# p7_1_3v3.net
KiCad netlist of a schematic drawn in EAGLE
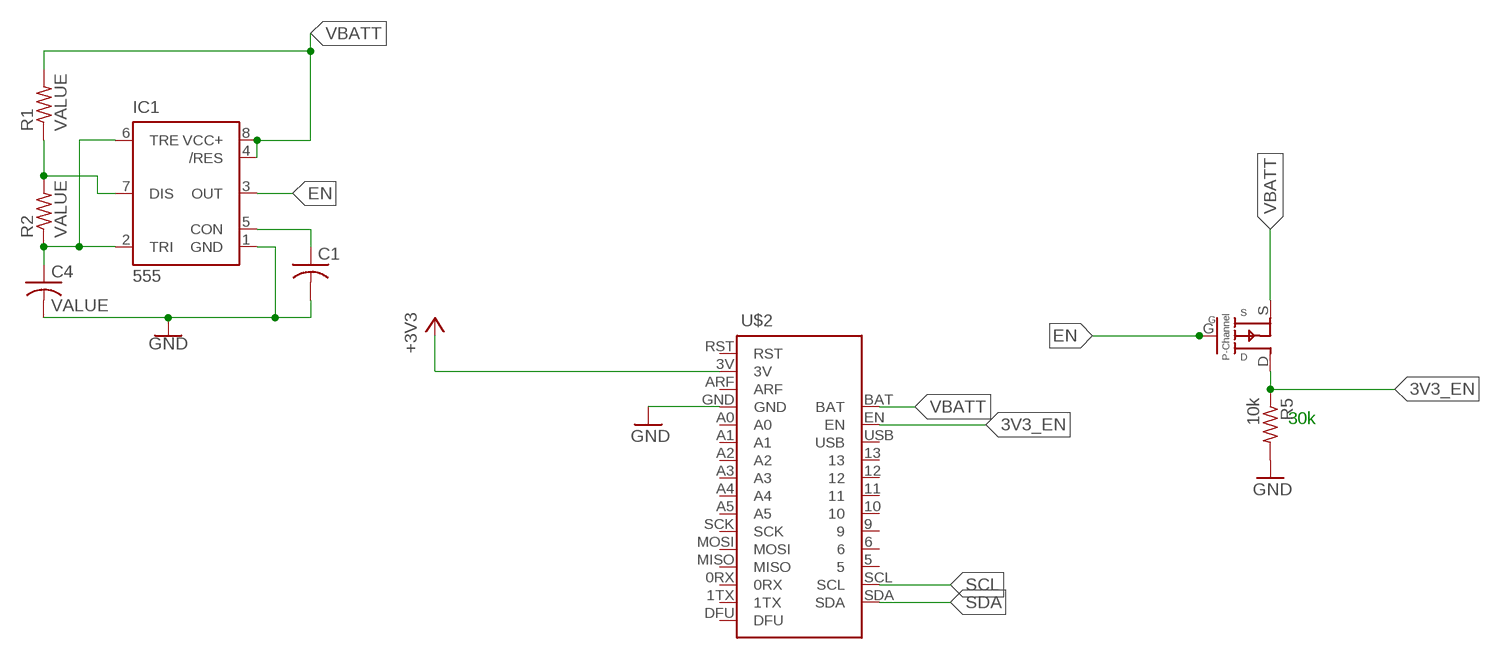
[diagram p0: schematic, sheet 1]

(export (version "E")
  (design (tool "Eeschema 10.0.6"))
  (components
    (comp (ref "C1")
      (value "C-USC1206")
      (footprint "eagle-import:C1206")
      (libsource (lib "eagle-import") (part "C-USC1206"))
    )
    (comp (ref "C4")
      (value "VALUE")
      (footprint "eagle-import:C1206")
      (libsource (lib "eagle-import") (part "C-USC1206"))
    )
    (comp (ref "IC1")
      (value "555")
      (footprint "eagle-import:DIP08")
      (libsource (lib "eagle-import") (part "555P"))
    )
    (comp (ref "Q2")
      (value "SSM3J3228R")
      (footprint "eagle-import:SOT-23-3")
      (libsource (lib "eagle-import") (part "SSM3J3228R"))
    )
    (comp (ref "R1")
      (value "VALUE")
      (footprint "eagle-import:R1206")
      (libsource (lib "eagle-import") (part "R-US_R1206"))
    )
    (comp (ref "R2")
      (value "VALUE")
      (footprint "eagle-import:R1206")
      (libsource (lib "eagle-import") (part "R-US_R1206"))
    )
    (comp (ref "R5")
      (value "10k")
      (footprint "eagle-import:R1206")
      (libsource (lib "eagle-import") (part "R-US_R1206"))
    )
    (comp (ref "U$2")
      (value "BLUEFRUIT_M0")
      (footprint "eagle-import:BLUEFRUIT_MO")
      (libsource (lib "eagle-import") (part "BLUEFRUIT_M0"))
    )
  )
  (nets
    (net (code "1") (name "+3V3") (class "Default")
      (node (ref "U$2") (pin "3V") (pinfunction "3V_3V") (pintype "bidirectional"))
    )
    (net (code "2") (name "3V3_EN") (class "Default")
      (node (ref "Q2") (pin "D") (pinfunction "D_D") (pintype "bidirectional"))
      (node (ref "R5") (pin "1") (pinfunction "1_1") (pintype "passive"))
      (node (ref "U$2") (pin "EN") (pinfunction "EN_EN") (pintype "bidirectional"))
    )
    (net (code "3") (name "EN") (class "Default")
      (node (ref "IC1") (pin "3") (pinfunction "OUT_3") (pintype "output"))
      (node (ref "Q2") (pin "G") (pinfunction "G_G") (pintype "bidirectional"))
    )
    (net (code "4") (name "GND") (class "Default")
      (node (ref "C1") (pin "2") (pinfunction "2_2") (pintype "passive"))
      (node (ref "C4") (pin "2") (pinfunction "2_2") (pintype "passive"))
      (node (ref "IC1") (pin "1") (pinfunction "GND_1") (pintype "power_in"))
      (node (ref "R5") (pin "2") (pinfunction "2_2") (pintype "passive"))
      (node (ref "U$2") (pin "GND") (pinfunction "GND_GND") (pintype "bidirectional"))
    )
    (net (code "5") (name "Net-(IC1-CON)") (class "Default")
      (node (ref "C1") (pin "1") (pinfunction "1_1") (pintype "passive"))
      (node (ref "IC1") (pin "5") (pinfunction "CON_5") (pintype "input"))
    )
    (net (code "6") (name "Net-(IC1-DIS)") (class "Default")
      (node (ref "IC1") (pin "7") (pinfunction "DIS_7") (pintype "input"))
      (node (ref "R1") (pin "1") (pinfunction "1_1") (pintype "passive"))
      (node (ref "R2") (pin "2") (pinfunction "2_2") (pintype "passive"))
    )
    (net (code "7") (name "Net-(IC1-TRE)") (class "Default")
      (node (ref "C4") (pin "1") (pinfunction "1_1") (pintype "passive"))
      (node (ref "IC1") (pin "2") (pinfunction "TRI_2") (pintype "input"))
      (node (ref "IC1") (pin "6") (pinfunction "TRE_6") (pintype "input"))
      (node (ref "R2") (pin "1") (pinfunction "1_1") (pintype "passive"))
    )
    (net (code "8") (name "SCL") (class "Default")
      (node (ref "U$2") (pin "SCL") (pinfunction "SCL_SCL") (pintype "bidirectional"))
    )
    (net (code "9") (name "SDA") (class "Default")
      (node (ref "U$2") (pin "SDA") (pinfunction "SDA_SDA") (pintype "bidirectional"))
    )
    (net (code "10") (name "VBATT") (class "Default")
      (node (ref "IC1") (pin "4") (pinfunction "/RES_4") (pintype "input"))
      (node (ref "IC1") (pin "8") (pinfunction "VCC+_8") (pintype "power_in"))
      (node (ref "Q2") (pin "S") (pinfunction "S_S") (pintype "bidirectional"))
      (node (ref "R1") (pin "2") (pinfunction "2_2") (pintype "passive"))
      (node (ref "U$2") (pin "BAT") (pinfunction "BAT_BAT") (pintype "bidirectional"))
    )
    (net (code "11") (name "unconnected-(U$2-Pad0RX)") (class "Default")
      (node (ref "U$2") (pin "0RX") (pinfunction "0RX_0RX") (pintype "bidirectional"))
    )
    (net (code "12") (name "unconnected-(U$2-Pad1TX)") (class "Default")
      (node (ref "U$2") (pin "1TX") (pinfunction "1TX_1TX") (pintype "bidirectional"))
    )
    (net (code "13") (name "unconnected-(U$2-Pad5)") (class "Default")
      (node (ref "U$2") (pin "5") (pinfunction "5_5") (pintype "bidirectional"))
    )
    (net (code "14") (name "unconnected-(U$2-Pad6)") (class "Default")
      (node (ref "U$2") (pin "6") (pinfunction "6_6") (pintype "bidirectional"))
    )
    (net (code "15") (name "unconnected-(U$2-Pad9)") (class "Default")
      (node (ref "U$2") (pin "9") (pinfunction "9_9") (pintype "bidirectional"))
    )
    (net (code "16") (name "unconnected-(U$2-Pad10)") (class "Default")
      (node (ref "U$2") (pin "10") (pinfunction "10_10") (pintype "bidirectional"))
    )
    (net (code "17") (name "unconnected-(U$2-Pad11)") (class "Default")
      (node (ref "U$2") (pin "11") (pinfunction "11_11") (pintype "bidirectional"))
    )
    (net (code "18") (name "unconnected-(U$2-Pad12)") (class "Default")
      (node (ref "U$2") (pin "12") (pinfunction "12_12") (pintype "bidirectional"))
    )
    (net (code "19") (name "unconnected-(U$2-Pad13)") (class "Default")
      (node (ref "U$2") (pin "13") (pinfunction "13_13") (pintype "bidirectional"))
    )
    (net (code "20") (name "unconnected-(U$2-PadA0)") (class "Default")
      (node (ref "U$2") (pin "A0") (pinfunction "A0_A0") (pintype "bidirectional"))
    )
    (net (code "21") (name "unconnected-(U$2-PadA1)") (class "Default")
      (node (ref "U$2") (pin "A1") (pinfunction "A1_A1") (pintype "bidirectional"))
    )
    (net (code "22") (name "unconnected-(U$2-PadA2)") (class "Default")
      (node (ref "U$2") (pin "A2") (pinfunction "A2_A2") (pintype "bidirectional"))
    )
    (net (code "23") (name "unconnected-(U$2-PadA3)") (class "Default")
      (node (ref "U$2") (pin "A3") (pinfunction "A3_A3") (pintype "bidirectional"))
    )
    (net (code "24") (name "unconnected-(U$2-PadA4)") (class "Default")
      (node (ref "U$2") (pin "A4") (pinfunction "A4_A4") (pintype "bidirectional"))
    )
    (net (code "25") (name "unconnected-(U$2-PadA5)") (class "Default")
      (node (ref "U$2") (pin "A5") (pinfunction "A5_A5") (pintype "bidirectional"))
    )
    (net (code "26") (name "unconnected-(U$2-PadARF)") (class "Default")
      (node (ref "U$2") (pin "ARF") (pinfunction "ARF_ARF") (pintype "bidirectional"))
    )
    (net (code "27") (name "unconnected-(U$2-PadDFU)") (class "Default")
      (node (ref "U$2") (pin "DFU") (pinfunction "DFU_DFU") (pintype "bidirectional"))
    )
    (net (code "28") (name "unconnected-(U$2-PadMISO)") (class "Default")
      (node (ref "U$2") (pin "MISO") (pinfunction "MISO_MISO") (pintype "bidirectional"))
    )
    (net (code "29") (name "unconnected-(U$2-PadMOSI)") (class "Default")
      (node (ref "U$2") (pin "MOSI") (pinfunction "MOSI_MOSI") (pintype "bidirectional"))
    )
    (net (code "30") (name "unconnected-(U$2-PadRST)") (class "Default")
      (node (ref "U$2") (pin "RST") (pinfunction "RST_RST") (pintype "bidirectional"))
    )
    (net (code "31") (name "unconnected-(U$2-PadSCK)") (class "Default")
      (node (ref "U$2") (pin "SCK") (pinfunction "SCK_SCK") (pintype "bidirectional"))
    )
    (net (code "32") (name "unconnected-(U$2-PadUSB)") (class "Default")
      (node (ref "U$2") (pin "USB") (pinfunction "USB_USB") (pintype "bidirectional"))
    )
  )
)
